# SCH_ESP8266_2025-04-25.net
KiCad netlist of a schematic drawn in EasyEDA
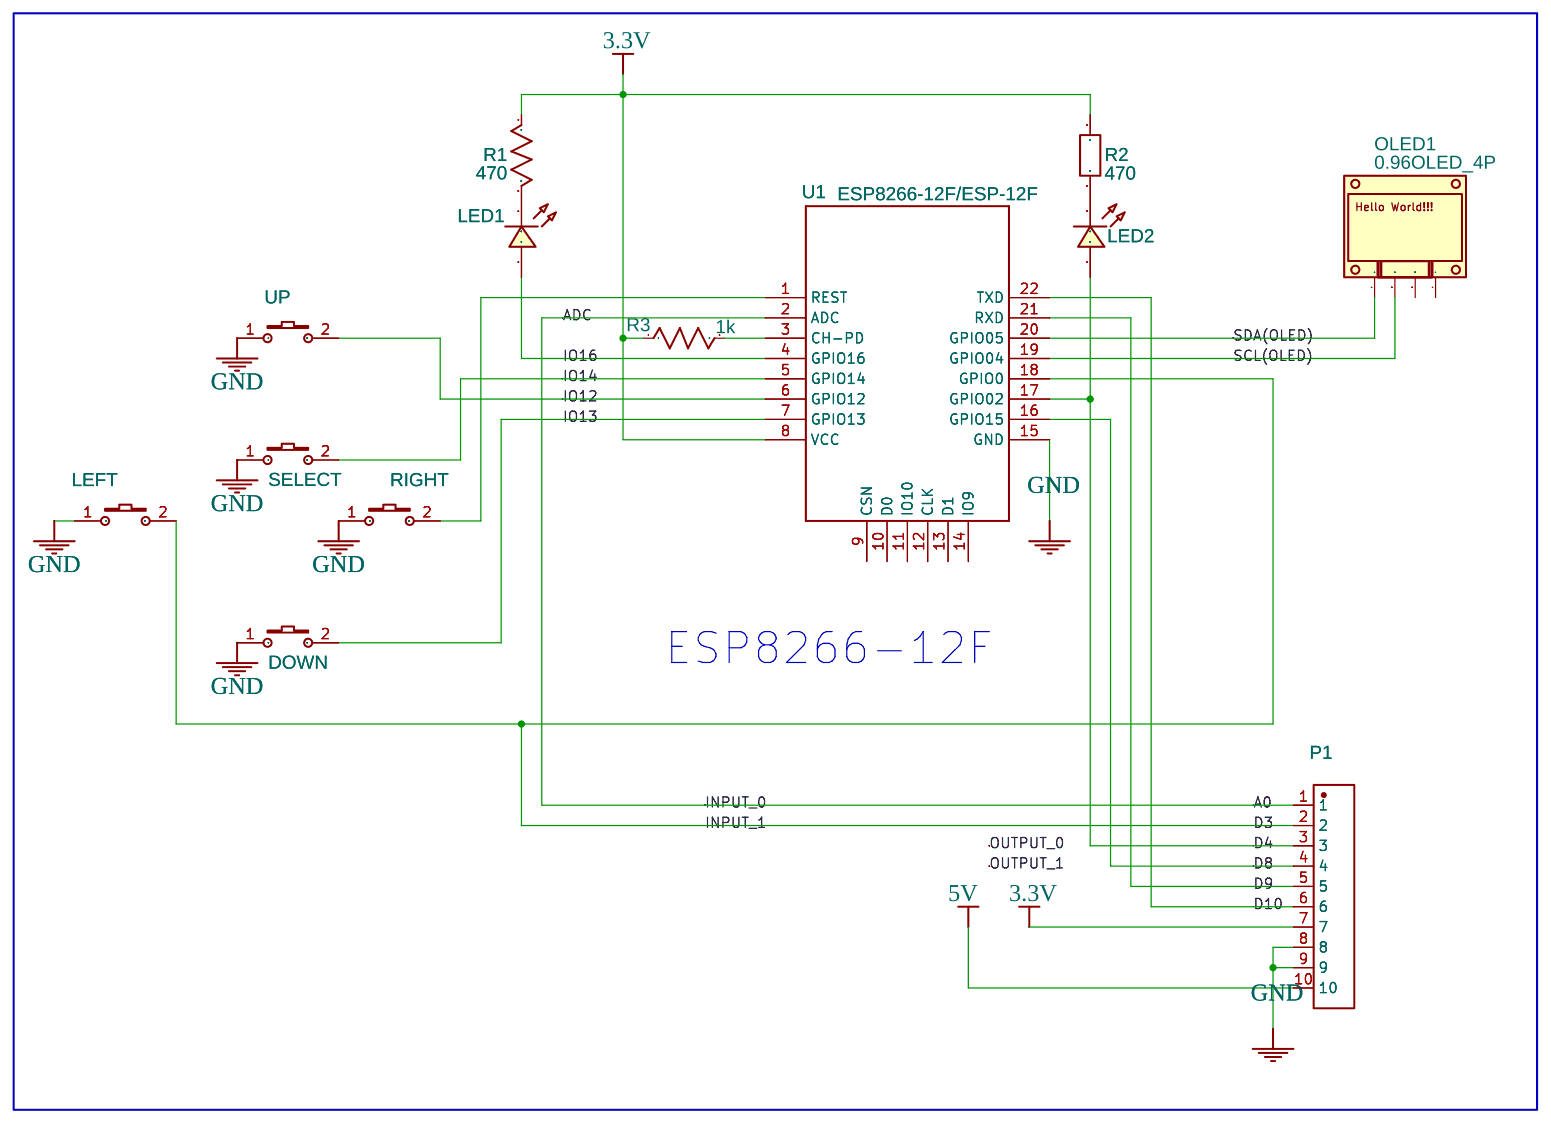
[diagram p0: ESP8266]
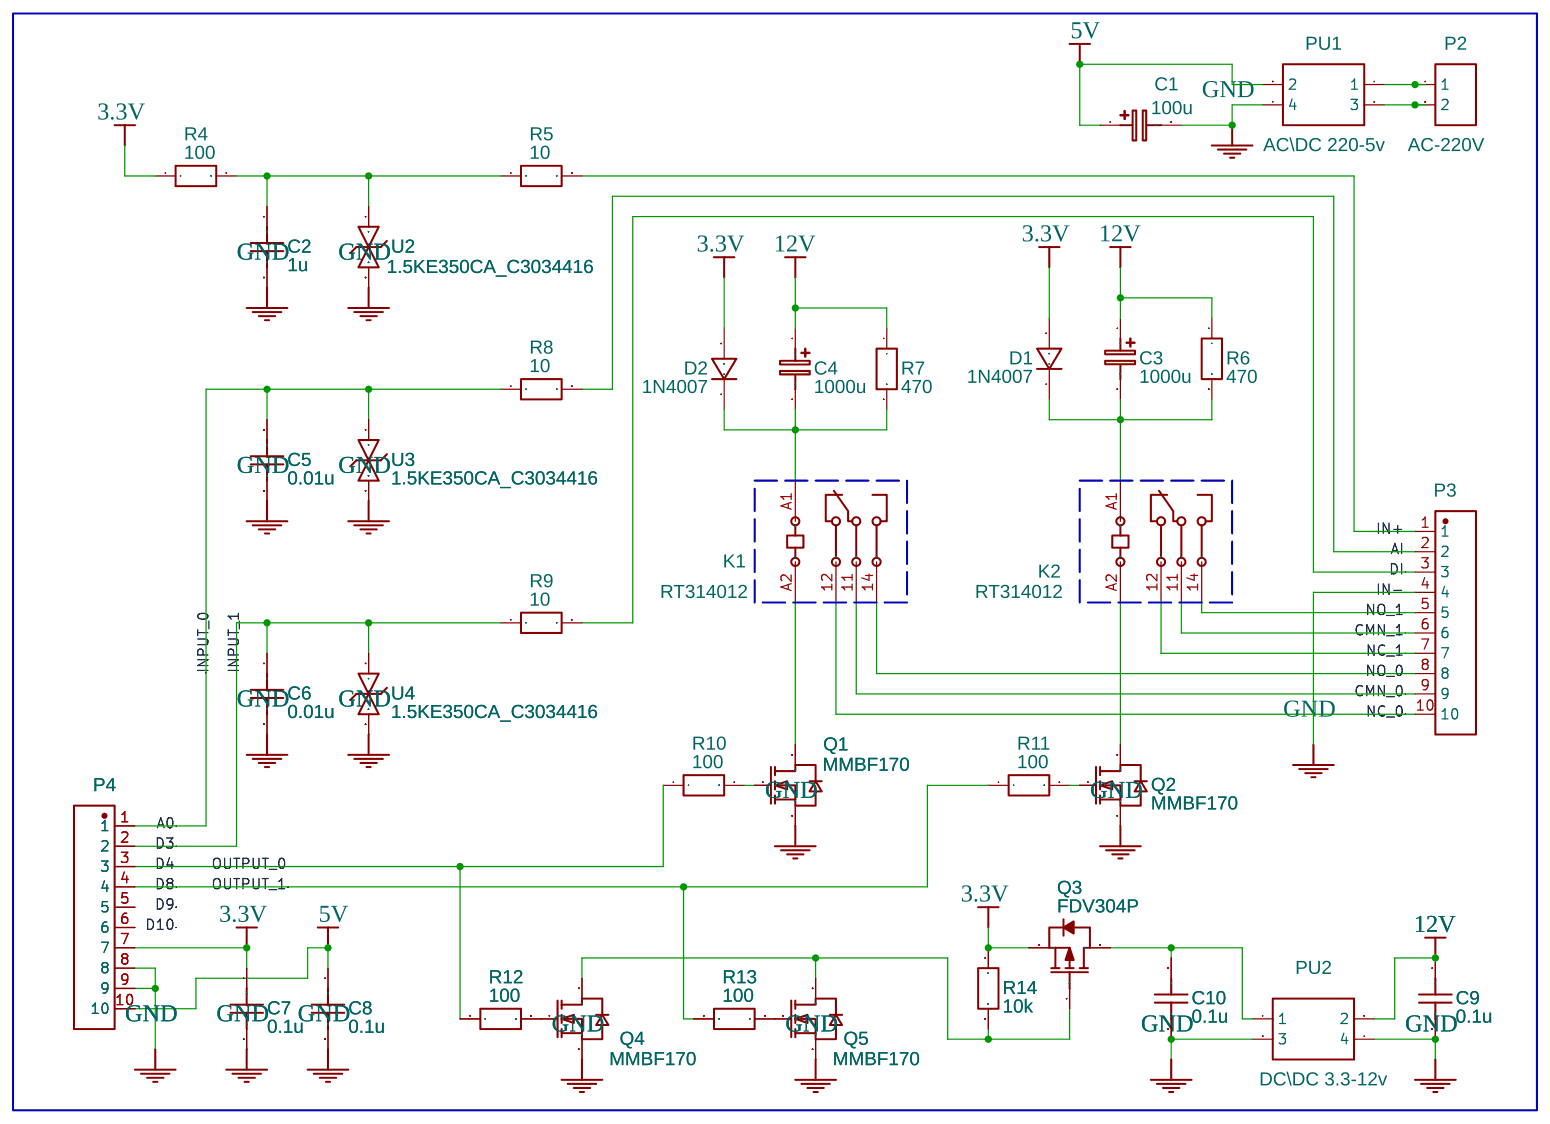
[diagram p1: Peripheral]
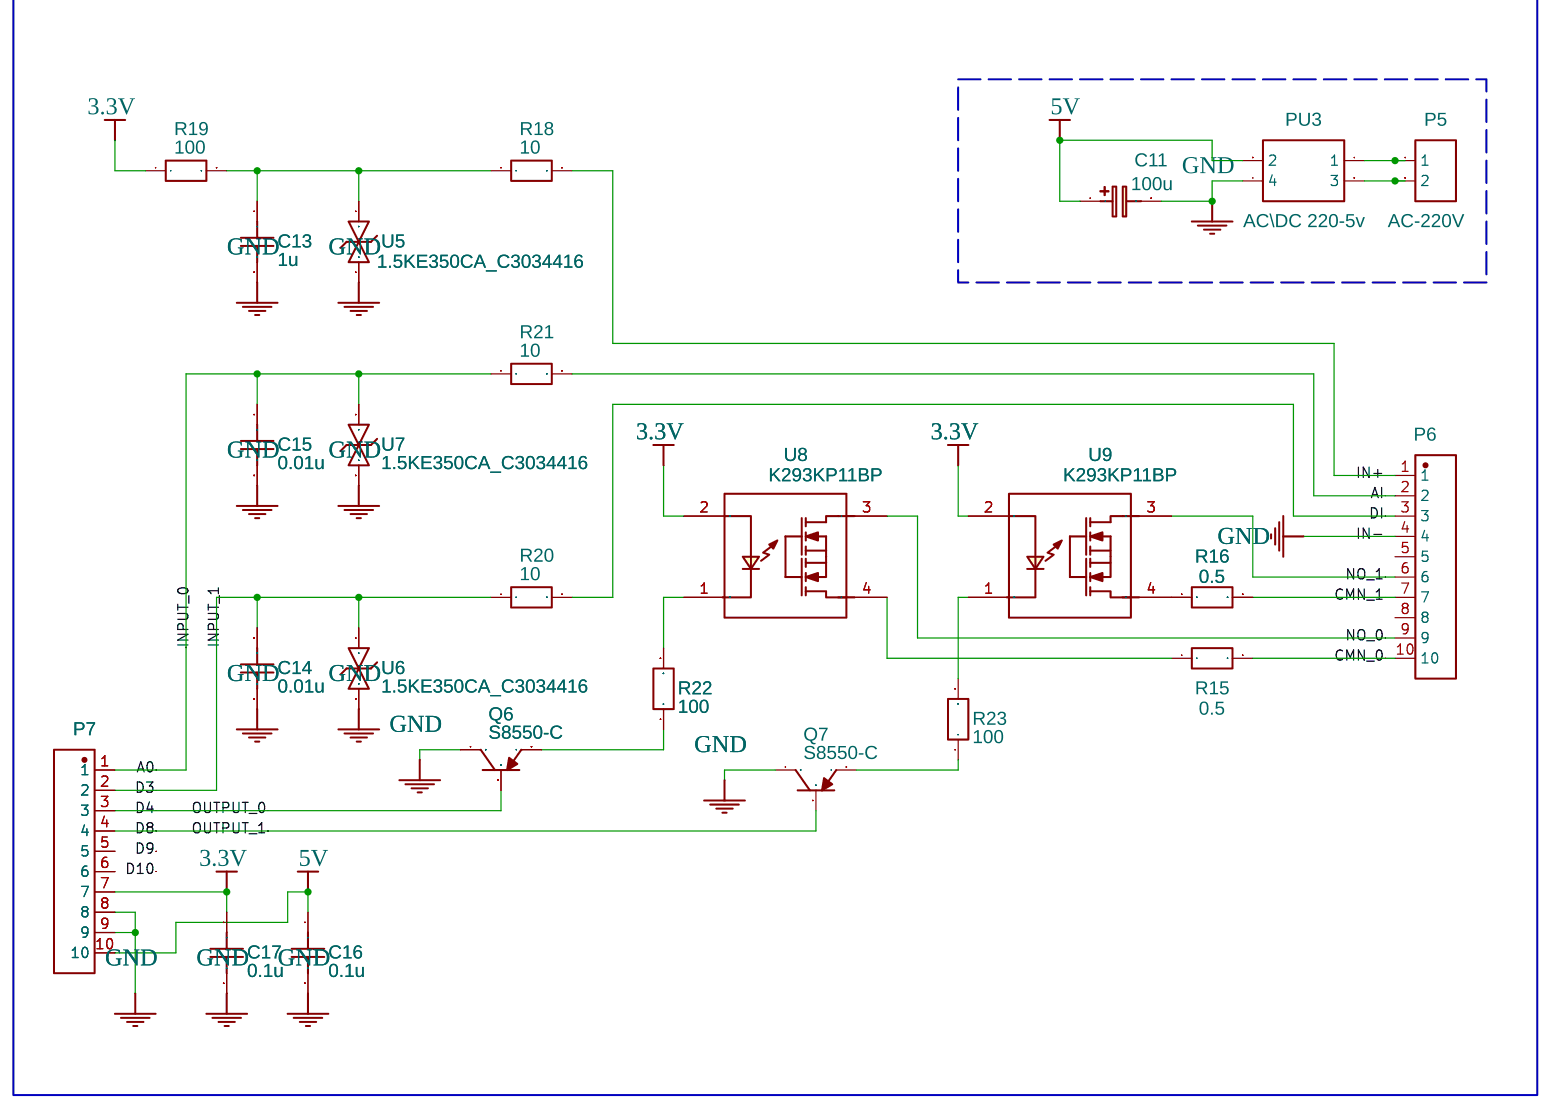
[diagram p2: Peripheral_SolidR]

(export (version "E")
  (design (tool "Eeschema 10.0.6"))
  (components
    (comp (ref "DOWN")
      (value "K2-3.6×6.1_SMD")
      (fields (field (name "Manufacturer Part") "K2-1107ST-A4SW-06"))
      (libsource (lib "") (part "K2-3.6×6.1_SMD_2"))
    )
    (comp (ref "LED1")
      (value "LED-0603_R")
      (fields
        (field (name "Manufacturer Part") "19-217/R6C-AL1M2VY/3T")
        (field (name "Manufacturer") "EVERLIGHT(台湾亿光)")
      )
      (libsource (lib "") (part "LED-0603_R"))
    )
    (comp (ref "LED2")
      (value "LED-0603_R")
      (fields
        (field (name "Manufacturer Part") "19-217/R6C-AL1M2VY/3T")
        (field (name "Manufacturer") "EVERLIGHT(台湾亿光)")
      )
      (libsource (lib "") (part "LED-0603_R"))
    )
    (comp (ref "LEFT")
      (value "K2-3.6×6.1_SMD")
      (fields (field (name "Manufacturer Part") "K2-1107ST-A4SW-06"))
      (libsource (lib "") (part "K2-3.6×6.1_SMD"))
    )
    (comp (ref "OLED1") (value "0.96OLED_4P") (libsource (lib "") (part "0.96OLED_4P")))
    (comp (ref "P1")
      (value "MTP310-1110S1")
      (fields (field (name "Manufacturer") "MINTRON(明硕)"))
      (libsource (lib "") (part "MTP310-1110S1"))
    )
    (comp (ref "R1")
      (value "470")
      (fields (field (name "Manufacturer Part") "?"))
      (libsource (lib "") (part "Resistor_1"))
    )
    (comp (ref "R2") (value "470") (libsource (lib "") (part "R_0603_EU")))
    (comp (ref "R3")
      (value "1k")
      (fields (field (name "Manufacturer Part") "?"))
      (libsource (lib "") (part "Resistor"))
    )
    (comp (ref "RIGHT")
      (value "K2-3.6×6.1_SMD")
      (fields (field (name "Manufacturer Part") "K2-1107ST-A4SW-06"))
      (libsource (lib "") (part "K2-3.6×6.1_SMD_4"))
    )
    (comp (ref "SELECT")
      (value "K2-3.6×6.1_SMD")
      (fields (field (name "Manufacturer Part") "K2-1107ST-A4SW-06"))
      (libsource (lib "") (part "K2-3.6×6.1_SMD_1"))
    )
    (comp (ref "U1")
      (value "ESP8266-12F/ESP-12F")
      (fields (field (name "Manufacturer Part") "ESP8266-12E/ESP-12E"))
      (libsource (lib "") (part "Unknown_1020_210"))
    )
    (comp (ref "UP")
      (value "K2-3.6×6.1_SMD")
      (fields (field (name "Manufacturer Part") "K2-1107ST-A4SW-06"))
      (libsource (lib "") (part "K2-3.6×6.1_SMD_3"))
    )
    (comp (ref "C1") (value "100u") (libsource (lib "") (part "C_Tan_SMD_A_EU_1")))
    (comp (ref "C2") (value "1u") (libsource (lib "") (part "C_0603_US")))
    (comp (ref "C3") (value "1000u") (libsource (lib "") (part "C_Tan_SMD_A_EU_2")))
    (comp (ref "C4") (value "1000u") (libsource (lib "") (part "C_Tan_SMD_A_EU")))
    (comp (ref "C5") (value "0.01u") (libsource (lib "") (part "C_0603_US")))
    (comp (ref "C6") (value "0.01u") (libsource (lib "") (part "C_0603_US")))
    (comp (ref "C7") (value "0.1u") (libsource (lib "") (part "C_0603_US")))
    (comp (ref "C8") (value "0.1u") (libsource (lib "") (part "C_0603_US")))
    (comp (ref "C9") (value "0.1u") (libsource (lib "") (part "C_0603_US")))
    (comp (ref "C10") (value "0.1u") (libsource (lib "") (part "C_0603_US_1")))
    (comp (ref "D1")
      (value "1N4007")
      (fields (field (name "Manufacturer") "SEMTECH"))
      (libsource (lib "") (part "1N4007"))
    )
    (comp (ref "D2")
      (value "1N4007")
      (fields (field (name "Manufacturer") "SEMTECH"))
      (libsource (lib "") (part "1N4007"))
    )
    (comp (ref "K1")
      (value "RT314012")
      (fields
        (field (name "Manufacturer Part") "RT314012F")
        (field (name "Manufacturer") "TE Connectivity(美国泰科)")
      )
      (libsource (lib "") (part "RT314012F"))
    )
    (comp (ref "K2")
      (value "RT314012")
      (fields
        (field (name "Manufacturer Part") "RT314012F")
        (field (name "Manufacturer") "TE Connectivity(美国泰科)")
      )
      (libsource (lib "") (part "RT314012F"))
    )
    (comp (ref "P2") (value "AC-220V") (libsource (lib "") (part "CONN-TH_2P-P5.00")))
    (comp (ref "P3")
      (value "MTP310-1110S1")
      (fields (field (name "Manufacturer") "MINTRON(明硕)"))
      (libsource (lib "") (part "MTP310-1110S1"))
    )
    (comp (ref "P4")
      (value "MTP310-1110S1")
      (fields (field (name "Manufacturer") "MINTRON(明硕)"))
      (libsource (lib "") (part "MTP310-1110S1_1"))
    )
    (comp (ref "PU1") (value "AC\\DC 220-5v") (libsource (lib "") (part "HDR-M-2.54_2x2_1")))
    (comp (ref "PU2") (value "DC\\DC 3.3-12v") (libsource (lib "") (part "HDR-M-2.54_2x2")))
    (comp (ref "Q1")
      (value "MMBF170")
      (fields (field (name "Manufacturer Part") "MMBF170Q-13-F") (field (name "Manufacturer") "DIODES(美台)"))
      (libsource (lib "") (part "MMBF170Q-13-F"))
    )
    (comp (ref "Q2")
      (value "MMBF170")
      (fields (field (name "Manufacturer Part") "MMBF170Q-13-F") (field (name "Manufacturer") "DIODES(美台)"))
      (libsource (lib "") (part "MMBF170Q-13-F"))
    )
    (comp (ref "Q3")
      (value "FDV304P")
      (fields (field (name "Manufacturer") "TECH PUBLIC(台舟)"))
      (libsource (lib "") (part "FDV304P_C7419961"))
    )
    (comp (ref "Q4")
      (value "MMBF170")
      (fields (field (name "Manufacturer Part") "MMBF170Q-13-F") (field (name "Manufacturer") "DIODES(美台)"))
      (libsource (lib "") (part "MMBF170Q-13-F"))
    )
    (comp (ref "Q5")
      (value "MMBF170")
      (fields (field (name "Manufacturer Part") "MMBF170Q-13-F") (field (name "Manufacturer") "DIODES(美台)"))
      (libsource (lib "") (part "MMBF170Q-13-F"))
    )
    (comp (ref "R4") (value "100") (libsource (lib "") (part "R_0603_EU")))
    (comp (ref "R5") (value "10") (libsource (lib "") (part "R_0603_EU")))
    (comp (ref "R6") (value "470") (libsource (lib "") (part "R_0603_EU_1")))
    (comp (ref "R7") (value "470") (libsource (lib "") (part "R_0603_EU_1")))
    (comp (ref "R8") (value "10") (libsource (lib "") (part "R_0603_EU")))
    (comp (ref "R9") (value "10") (libsource (lib "") (part "R_0603_EU")))
    (comp (ref "R10") (value "100") (libsource (lib "") (part "R_0603_EU")))
    (comp (ref "R11") (value "100") (libsource (lib "") (part "R_0603_EU")))
    (comp (ref "R12") (value "100") (libsource (lib "") (part "R_0603_EU")))
    (comp (ref "R13") (value "100") (libsource (lib "") (part "R_0603_EU")))
    (comp (ref "R14") (value "10k") (libsource (lib "") (part "R_0603_EU_1")))
    (comp (ref "U2")
      (value "1.5KE350CA_C3034416")
      (fields (field (name "Manufacturer Part") "1.5KE350CA") (field (name "Manufacturer") "Liown(里阳半导体)"))
      (libsource (lib "") (part "1.5KE350CA_C3034416"))
    )
    (comp (ref "U3")
      (value "1.5KE350CA_C3034416")
      (fields (field (name "Manufacturer Part") "1.5KE350CA") (field (name "Manufacturer") "Liown(里阳半导体)"))
      (libsource (lib "") (part "1.5KE350CA_C3034416"))
    )
    (comp (ref "U4")
      (value "1.5KE350CA_C3034416")
      (fields (field (name "Manufacturer Part") "1.5KE350CA") (field (name "Manufacturer") "Liown(里阳半导体)"))
      (libsource (lib "") (part "1.5KE350CA_C3034416"))
    )
    (comp (ref "C11") (value "100u") (libsource (lib "") (part "C_Tan_SMD_A_EU")))
    (comp (ref "C13") (value "1u") (libsource (lib "") (part "C_0603_US")))
    (comp (ref "C14") (value "0.01u") (libsource (lib "") (part "C_0603_US")))
    (comp (ref "C15") (value "0.01u") (libsource (lib "") (part "C_0603_US")))
    (comp (ref "C16") (value "0.1u") (libsource (lib "") (part "C_0603_US")))
    (comp (ref "C17") (value "0.1u") (libsource (lib "") (part "C_0603_US")))
    (comp (ref "P5") (value "AC-220V") (libsource (lib "") (part "CONN-TH_2P-P5.00")))
    (comp (ref "P6")
      (value "MTP310-1110S1")
      (fields (field (name "Manufacturer") "MINTRON(明硕)"))
      (libsource (lib "") (part "MTP310-1110S1_1"))
    )
    (comp (ref "P7")
      (value "MTP310-1110S1")
      (fields (field (name "Manufacturer") "MINTRON(明硕)"))
      (libsource (lib "") (part "MTP310-1110S1"))
    )
    (comp (ref "PU3") (value "AC\\DC 220-5v") (libsource (lib "") (part "HDR-M-2.54_2x2")))
    (comp (ref "Q6")
      (value "S8550-C")
      (fields (field (name "Manufacturer") "BLUE ROCKET(蓝箭)"))
      (libsource (lib "") (part "S8550-C"))
    )
    (comp (ref "Q7")
      (value "S8550-C")
      (fields (field (name "Manufacturer") "BLUE ROCKET(蓝箭)"))
      (libsource (lib "") (part "S8550-C"))
    )
    (comp (ref "R15") (value "0.5") (libsource (lib "") (part "R_0603_EU")))
    (comp (ref "R16") (value "0.5") (libsource (lib "") (part "R_0603_EU")))
    (comp (ref "R18") (value "10") (libsource (lib "") (part "R_0603_EU")))
    (comp (ref "R19") (value "100") (libsource (lib "") (part "R_0603_EU")))
    (comp (ref "R20") (value "10") (libsource (lib "") (part "R_0603_EU")))
    (comp (ref "R21") (value "10") (libsource (lib "") (part "R_0603_EU")))
    (comp (ref "R22") (value "100") (libsource (lib "") (part "R_0603_EU_1")))
    (comp (ref "R23") (value "100") (libsource (lib "") (part "R_0603_EU_1")))
    (comp (ref "U5")
      (value "1.5KE350CA_C3034416")
      (fields (field (name "Manufacturer Part") "1.5KE350CA") (field (name "Manufacturer") "Liown(里阳半导体)"))
      (libsource (lib "") (part "1.5KE350CA_C3034416"))
    )
    (comp (ref "U6")
      (value "1.5KE350CA_C3034416")
      (fields (field (name "Manufacturer Part") "1.5KE350CA") (field (name "Manufacturer") "Liown(里阳半导体)"))
      (libsource (lib "") (part "1.5KE350CA_C3034416"))
    )
    (comp (ref "U7")
      (value "1.5KE350CA_C3034416")
      (fields (field (name "Manufacturer Part") "1.5KE350CA") (field (name "Manufacturer") "Liown(里阳半导体)"))
      (libsource (lib "") (part "1.5KE350CA_C3034416"))
    )
    (comp (ref "U8")
      (value "K293KP11BP")
      (fields (field (name "Manufacturer Part") "CPC1916Y") (field (name "Manufacturer") "Littelfuse/IXYS"))
      (libsource (lib "") (part "CPC1916Y"))
    )
    (comp (ref "U9")
      (value "K293KP11BP")
      (fields (field (name "Manufacturer Part") "CPC1916Y") (field (name "Manufacturer") "Littelfuse/IXYS"))
      (libsource (lib "") (part "CPC1916Y"))
    )
  )
  (nets
    (net (code "1") (name "3.3V") (class "Default")
      (node (ref "C17") (pin "1") (pinfunction "1_1") (pintype "unspecified"))
      (node (ref "C7") (pin "1") (pinfunction "1_1") (pintype "unspecified"))
      (node (ref "D1") (pin "2") (pinfunction "2_2") (pintype "unspecified"))
      (node (ref "D2") (pin "2") (pinfunction "2_2") (pintype "unspecified"))
      (node (ref "P1") (pin "7") (pinfunction "7_7") (pintype "unspecified"))
      (node (ref "P4") (pin "7") (pinfunction "7_7") (pintype "unspecified"))
      (node (ref "P7") (pin "7") (pinfunction "7_7") (pintype "unspecified"))
      (node (ref "Q3") (pin "2") (pinfunction "S_2") (pintype "unspecified"))
      (node (ref "R1") (pin "1") (pinfunction "1_1") (pintype "unspecified"))
      (node (ref "R14") (pin "1") (pinfunction "1_1") (pintype "unspecified"))
      (node (ref "R19") (pin "1") (pinfunction "1_1") (pintype "unspecified"))
      (node (ref "R2") (pin "1") (pinfunction "1_1") (pintype "unspecified"))
      (node (ref "R3") (pin "1") (pinfunction "1_1") (pintype "unspecified"))
      (node (ref "R4") (pin "1") (pinfunction "1_1") (pintype "unspecified"))
      (node (ref "U1") (pin "8") (pinfunction "VCC_8") (pintype "unspecified"))
      (node (ref "U8") (pin "2") (pinfunction "+C_2") (pintype "unspecified"))
      (node (ref "U9") (pin "2") (pinfunction "+C_2") (pintype "unspecified"))
    )
    (net (code "2") (name "5V") (class "Default")
      (node (ref "C1") (pin "1") (pinfunction "1_1") (pintype "unspecified"))
      (node (ref "C11") (pin "1") (pinfunction "1_1") (pintype "unspecified"))
      (node (ref "C16") (pin "1") (pinfunction "1_1") (pintype "unspecified"))
      (node (ref "C8") (pin "1") (pinfunction "1_1") (pintype "unspecified"))
      (node (ref "P1") (pin "10") (pinfunction "10_10") (pintype "unspecified"))
      (node (ref "P4") (pin "10") (pinfunction "10_10") (pintype "unspecified"))
      (node (ref "P7") (pin "10") (pinfunction "10_10") (pintype "unspecified"))
      (node (ref "PU1") (pin "2") (pinfunction "2_2") (pintype "input"))
      (node (ref "PU3") (pin "2") (pinfunction "2_2") (pintype "input"))
    )
    (net (code "3") (name "12V") (class "Default")
      (node (ref "C3") (pin "1") (pinfunction "1_1") (pintype "unspecified"))
      (node (ref "C4") (pin "1") (pinfunction "1_1") (pintype "unspecified"))
      (node (ref "C9") (pin "1") (pinfunction "1_1") (pintype "unspecified"))
      (node (ref "PU2") (pin "2") (pinfunction "2_2") (pintype "input"))
      (node (ref "R6") (pin "1") (pinfunction "1_1") (pintype "unspecified"))
      (node (ref "R7") (pin "1") (pinfunction "1_1") (pintype "unspecified"))
    )
    (net (code "4") (name "A0") (class "Default")
      (node (ref "C15") (pin "1") (pinfunction "1_1") (pintype "unspecified"))
      (node (ref "C5") (pin "1") (pinfunction "1_1") (pintype "unspecified"))
      (node (ref "P1") (pin "1") (pinfunction "1_1") (pintype "unspecified"))
      (node (ref "P4") (pin "1") (pinfunction "1_1") (pintype "unspecified"))
      (node (ref "P7") (pin "1") (pinfunction "1_1") (pintype "unspecified"))
      (node (ref "R21") (pin "1") (pinfunction "1_1") (pintype "unspecified"))
      (node (ref "R8") (pin "1") (pinfunction "1_1") (pintype "unspecified"))
      (node (ref "U1") (pin "2") (pinfunction "ADC_2") (pintype "unspecified"))
      (node (ref "U3") (pin "1") (pinfunction "1_1") (pintype "unspecified"))
      (node (ref "U7") (pin "1") (pinfunction "1_1") (pintype "unspecified"))
    )
    (net (code "5") (name "AI") (class "Default")
      (node (ref "P3") (pin "2") (pinfunction "2_2") (pintype "unspecified"))
      (node (ref "P6") (pin "2") (pinfunction "2_2") (pintype "unspecified"))
      (node (ref "R21") (pin "2") (pinfunction "2_2") (pintype "unspecified"))
      (node (ref "R8") (pin "2") (pinfunction "2_2") (pintype "unspecified"))
    )
    (net (code "6") (name "CMN_0") (class "Default")
      (node (ref "K1") (pin "11") (pinfunction "11_11") (pintype "unspecified"))
      (node (ref "P3") (pin "9") (pinfunction "9_9") (pintype "unspecified"))
      (node (ref "P6") (pin "10") (pinfunction "10_10") (pintype "unspecified"))
      (node (ref "R15") (pin "2") (pinfunction "2_2") (pintype "unspecified"))
    )
    (net (code "7") (name "CMN_1") (class "Default")
      (node (ref "K2") (pin "11") (pinfunction "11_11") (pintype "unspecified"))
      (node (ref "P3") (pin "6") (pinfunction "6_6") (pintype "unspecified"))
      (node (ref "P6") (pin "7") (pinfunction "7_7") (pintype "unspecified"))
      (node (ref "R16") (pin "2") (pinfunction "2_2") (pintype "unspecified"))
    )
    (net (code "8") (name "D3") (class "Default")
      (node (ref "C14") (pin "1") (pinfunction "1_1") (pintype "unspecified"))
      (node (ref "C6") (pin "1") (pinfunction "1_1") (pintype "unspecified"))
      (node (ref "LEFT") (pin "2") (pinfunction "2_2") (pintype "unspecified"))
      (node (ref "P1") (pin "2") (pinfunction "2_2") (pintype "unspecified"))
      (node (ref "P4") (pin "2") (pinfunction "2_2") (pintype "unspecified"))
      (node (ref "P7") (pin "2") (pinfunction "2_2") (pintype "unspecified"))
      (node (ref "R20") (pin "1") (pinfunction "1_1") (pintype "unspecified"))
      (node (ref "R9") (pin "1") (pinfunction "1_1") (pintype "unspecified"))
      (node (ref "U1") (pin "18") (pinfunction "GPIO0_18") (pintype "unspecified"))
      (node (ref "U4") (pin "1") (pinfunction "1_1") (pintype "unspecified"))
      (node (ref "U6") (pin "1") (pinfunction "1_1") (pintype "unspecified"))
    )
    (net (code "9") (name "D4") (class "Default")
      (node (ref "LED2") (pin "1") (pinfunction "1_1") (pintype "unspecified"))
      (node (ref "P1") (pin "3") (pinfunction "3_3") (pintype "unspecified"))
      (node (ref "P4") (pin "3") (pinfunction "3_3") (pintype "unspecified"))
      (node (ref "P7") (pin "3") (pinfunction "3_3") (pintype "unspecified"))
      (node (ref "Q6") (pin "2") (pinfunction "B_2") (pintype "input"))
      (node (ref "R10") (pin "1") (pinfunction "1_1") (pintype "unspecified"))
      (node (ref "R12") (pin "1") (pinfunction "1_1") (pintype "unspecified"))
      (node (ref "U1") (pin "17") (pinfunction "GPIO02_17") (pintype "unspecified"))
    )
    (net (code "10") (name "D8") (class "Default")
      (node (ref "P1") (pin "4") (pinfunction "4_4") (pintype "unspecified"))
      (node (ref "P4") (pin "4") (pinfunction "4_4") (pintype "unspecified"))
      (node (ref "P7") (pin "4") (pinfunction "4_4") (pintype "unspecified"))
      (node (ref "Q7") (pin "2") (pinfunction "B_2") (pintype "input"))
      (node (ref "R11") (pin "1") (pinfunction "1_1") (pintype "unspecified"))
      (node (ref "R13") (pin "1") (pinfunction "1_1") (pintype "unspecified"))
      (node (ref "U1") (pin "16") (pinfunction "GPIO15_16") (pintype "unspecified"))
    )
    (net (code "11") (name "D9") (class "Default")
      (node (ref "P1") (pin "5") (pinfunction "5_5") (pintype "unspecified"))
      (node (ref "U1") (pin "21") (pinfunction "RXD_21") (pintype "unspecified"))
    )
    (net (code "12") (name "D10") (class "Default")
      (node (ref "P1") (pin "6") (pinfunction "6_6") (pintype "unspecified"))
      (node (ref "U1") (pin "22") (pinfunction "TXD_22") (pintype "unspecified"))
    )
    (net (code "13") (name "DI") (class "Default")
      (node (ref "P3") (pin "3") (pinfunction "3_3") (pintype "unspecified"))
      (node (ref "P6") (pin "3") (pinfunction "3_3") (pintype "unspecified"))
      (node (ref "R20") (pin "2") (pinfunction "2_2") (pintype "unspecified"))
      (node (ref "R9") (pin "2") (pinfunction "2_2") (pintype "unspecified"))
    )
    (net (code "14") (name "IN+") (class "Default")
      (node (ref "P3") (pin "1") (pinfunction "1_1") (pintype "unspecified"))
      (node (ref "P6") (pin "1") (pinfunction "1_1") (pintype "unspecified"))
      (node (ref "R18") (pin "2") (pinfunction "2_2") (pintype "unspecified"))
      (node (ref "R5") (pin "2") (pinfunction "2_2") (pintype "unspecified"))
    )
    (net (code "15") (name "IN-") (class "Default")
      (node (ref "C1") (pin "2") (pinfunction "2_2") (pintype "unspecified"))
      (node (ref "C10") (pin "1") (pinfunction "1_1") (pintype "unspecified"))
      (node (ref "C11") (pin "2") (pinfunction "2_2") (pintype "unspecified"))
      (node (ref "C13") (pin "2") (pinfunction "2_2") (pintype "unspecified"))
      (node (ref "C14") (pin "2") (pinfunction "2_2") (pintype "unspecified"))
      (node (ref "C15") (pin "2") (pinfunction "2_2") (pintype "unspecified"))
      (node (ref "C16") (pin "2") (pinfunction "2_2") (pintype "unspecified"))
      (node (ref "C17") (pin "2") (pinfunction "2_2") (pintype "unspecified"))
      (node (ref "C2") (pin "2") (pinfunction "2_2") (pintype "unspecified"))
      (node (ref "C5") (pin "2") (pinfunction "2_2") (pintype "unspecified"))
      (node (ref "C6") (pin "2") (pinfunction "2_2") (pintype "unspecified"))
      (node (ref "C7") (pin "2") (pinfunction "2_2") (pintype "unspecified"))
      (node (ref "C8") (pin "2") (pinfunction "2_2") (pintype "unspecified"))
      (node (ref "C9") (pin "2") (pinfunction "2_2") (pintype "unspecified"))
      (node (ref "DOWN") (pin "1") (pinfunction "1_1") (pintype "unspecified"))
      (node (ref "LEFT") (pin "1") (pinfunction "1_1") (pintype "unspecified"))
      (node (ref "P1") (pin "8") (pinfunction "8_8") (pintype "unspecified"))
      (node (ref "P1") (pin "9") (pinfunction "9_9") (pintype "unspecified"))
      (node (ref "P3") (pin "4") (pinfunction "4_4") (pintype "unspecified"))
      (node (ref "P4") (pin "8") (pinfunction "8_8") (pintype "unspecified"))
      (node (ref "P4") (pin "9") (pinfunction "9_9") (pintype "unspecified"))
      (node (ref "P6") (pin "4") (pinfunction "4_4") (pintype "unspecified"))
      (node (ref "P7") (pin "8") (pinfunction "8_8") (pintype "unspecified"))
      (node (ref "P7") (pin "9") (pinfunction "9_9") (pintype "unspecified"))
      (node (ref "PU1") (pin "4") (pinfunction "4_4") (pintype "input"))
      (node (ref "PU2") (pin "3") (pinfunction "3_3") (pintype "input"))
      (node (ref "PU2") (pin "4") (pinfunction "4_4") (pintype "input"))
      (node (ref "PU3") (pin "4") (pinfunction "4_4") (pintype "input"))
      (node (ref "Q1") (pin "2") (pinfunction "S_2") (pintype "unspecified"))
      (node (ref "Q2") (pin "2") (pinfunction "S_2") (pintype "unspecified"))
      (node (ref "Q4") (pin "2") (pinfunction "S_2") (pintype "unspecified"))
      (node (ref "Q5") (pin "2") (pinfunction "S_2") (pintype "unspecified"))
      (node (ref "Q6") (pin "1") (pinfunction "C_1") (pintype "input"))
      (node (ref "Q7") (pin "1") (pinfunction "C_1") (pintype "input"))
      (node (ref "RIGHT") (pin "1") (pinfunction "1_1") (pintype "unspecified"))
      (node (ref "SELECT") (pin "1") (pinfunction "1_1") (pintype "unspecified"))
      (node (ref "U1") (pin "15") (pinfunction "GND_15") (pintype "unspecified"))
      (node (ref "U2") (pin "2") (pinfunction "2_2") (pintype "unspecified"))
      (node (ref "U3") (pin "2") (pinfunction "2_2") (pintype "unspecified"))
      (node (ref "U4") (pin "2") (pinfunction "2_2") (pintype "unspecified"))
      (node (ref "U5") (pin "2") (pinfunction "2_2") (pintype "unspecified"))
      (node (ref "U6") (pin "2") (pinfunction "2_2") (pintype "unspecified"))
      (node (ref "U7") (pin "2") (pinfunction "2_2") (pintype "unspecified"))
      (node (ref "UP") (pin "1") (pinfunction "1_1") (pintype "unspecified"))
    )
    (net (code "16") (name "IO12") (class "Default")
      (node (ref "U1") (pin "6") (pinfunction "GPIO12_6") (pintype "unspecified"))
      (node (ref "UP") (pin "2") (pinfunction "2_2") (pintype "unspecified"))
    )
    (net (code "17") (name "IO13") (class "Default")
      (node (ref "DOWN") (pin "2") (pinfunction "2_2") (pintype "unspecified"))
      (node (ref "U1") (pin "7") (pinfunction "GPIO13_7") (pintype "unspecified"))
    )
    (net (code "18") (name "IO14") (class "Default")
      (node (ref "SELECT") (pin "2") (pinfunction "2_2") (pintype "unspecified"))
      (node (ref "U1") (pin "5") (pinfunction "GPIO14_5") (pintype "unspecified"))
    )
    (net (code "19") (name "IO16") (class "Default")
      (node (ref "LED1") (pin "1") (pinfunction "1_1") (pintype "unspecified"))
      (node (ref "U1") (pin "4") (pinfunction "GPIO16_4") (pintype "unspecified"))
    )
    (net (code "20") (name "NC_0") (class "Default")
      (node (ref "K1") (pin "12") (pinfunction "12_12") (pintype "unspecified"))
      (node (ref "P3") (pin "10") (pinfunction "10_10") (pintype "unspecified"))
    )
    (net (code "21") (name "NC_1") (class "Default")
      (node (ref "K2") (pin "12") (pinfunction "12_12") (pintype "unspecified"))
      (node (ref "P3") (pin "7") (pinfunction "7_7") (pintype "unspecified"))
    )
    (net (code "22") (name "NO_0") (class "Default")
      (node (ref "K1") (pin "14") (pinfunction "14_14") (pintype "unspecified"))
      (node (ref "P3") (pin "8") (pinfunction "8_8") (pintype "unspecified"))
      (node (ref "P6") (pin "9") (pinfunction "9_9") (pintype "unspecified"))
      (node (ref "U8") (pin "3") (pinfunction "L_3") (pintype "unspecified"))
    )
    (net (code "23") (name "NO_1") (class "Default")
      (node (ref "K2") (pin "14") (pinfunction "14_14") (pintype "unspecified"))
      (node (ref "P3") (pin "5") (pinfunction "5_5") (pintype "unspecified"))
      (node (ref "P6") (pin "6") (pinfunction "6_6") (pintype "unspecified"))
      (node (ref "U9") (pin "3") (pinfunction "L_3") (pintype "unspecified"))
    )
    (net (code "24") (name "Net-(C2-Pad1)") (class "Default")
      (node (ref "C2") (pin "1") (pinfunction "1_1") (pintype "unspecified"))
      (node (ref "R4") (pin "2") (pinfunction "2_2") (pintype "unspecified"))
      (node (ref "R5") (pin "1") (pinfunction "1_1") (pintype "unspecified"))
      (node (ref "U2") (pin "1") (pinfunction "1_1") (pintype "unspecified"))
    )
    (net (code "25") (name "Net-(C3-Pad2)") (class "Default")
      (node (ref "C3") (pin "2") (pinfunction "2_2") (pintype "unspecified"))
      (node (ref "D1") (pin "1") (pinfunction "1_1") (pintype "unspecified"))
      (node (ref "K2") (pin "A1") (pinfunction "A1_A1") (pintype "unspecified"))
      (node (ref "R6") (pin "2") (pinfunction "2_2") (pintype "unspecified"))
    )
    (net (code "26") (name "Net-(C4-Pad2)") (class "Default")
      (node (ref "C4") (pin "2") (pinfunction "2_2") (pintype "unspecified"))
      (node (ref "D2") (pin "1") (pinfunction "1_1") (pintype "unspecified"))
      (node (ref "K1") (pin "A1") (pinfunction "A1_A1") (pintype "unspecified"))
      (node (ref "R7") (pin "2") (pinfunction "2_2") (pintype "unspecified"))
    )
    (net (code "27") (name "Net-(C13-Pad1)") (class "Default")
      (node (ref "C13") (pin "1") (pinfunction "1_1") (pintype "unspecified"))
      (node (ref "R18") (pin "1") (pinfunction "1_1") (pintype "unspecified"))
      (node (ref "R19") (pin "2") (pinfunction "2_2") (pintype "unspecified"))
      (node (ref "U5") (pin "1") (pinfunction "1_1") (pintype "unspecified"))
    )
    (net (code "28") (name "Net-(LED1-Pad2)") (class "Default")
      (node (ref "LED1") (pin "2") (pinfunction "2_2") (pintype "unspecified"))
      (node (ref "R1") (pin "2") (pinfunction "2_2") (pintype "unspecified"))
    )
    (net (code "29") (name "Net-(LED2-Pad2)") (class "Default")
      (node (ref "LED2") (pin "2") (pinfunction "2_2") (pintype "unspecified"))
      (node (ref "R2") (pin "2") (pinfunction "2_2") (pintype "unspecified"))
    )
    (net (code "30") (name "Net-(P2-Pad1)") (class "Default")
      (node (ref "P2") (pin "1") (pinfunction "1_1") (pintype "unspecified"))
      (node (ref "PU1") (pin "1") (pinfunction "1_1") (pintype "input"))
    )
    (net (code "31") (name "Net-(P2-Pad2)") (class "Default")
      (node (ref "P2") (pin "2") (pinfunction "2_2") (pintype "unspecified"))
      (node (ref "PU1") (pin "3") (pinfunction "3_3") (pintype "input"))
    )
    (net (code "32") (name "Net-(P5-Pad1)") (class "Default")
      (node (ref "P5") (pin "1") (pinfunction "1_1") (pintype "unspecified"))
      (node (ref "PU3") (pin "1") (pinfunction "1_1") (pintype "input"))
    )
    (net (code "33") (name "Net-(P5-Pad2)") (class "Default")
      (node (ref "P5") (pin "2") (pinfunction "2_2") (pintype "unspecified"))
      (node (ref "PU3") (pin "3") (pinfunction "3_3") (pintype "input"))
    )
    (net (code "34") (name "Net-(Q1-D)") (class "Default")
      (node (ref "K1") (pin "A2") (pinfunction "A2_A2") (pintype "unspecified"))
      (node (ref "Q1") (pin "3") (pinfunction "D_3") (pintype "unspecified"))
    )
    (net (code "35") (name "Net-(Q1-G)") (class "Default")
      (node (ref "Q1") (pin "1") (pinfunction "G_1") (pintype "unspecified"))
      (node (ref "R10") (pin "2") (pinfunction "2_2") (pintype "unspecified"))
    )
    (net (code "36") (name "Net-(Q2-D)") (class "Default")
      (node (ref "K2") (pin "A2") (pinfunction "A2_A2") (pintype "unspecified"))
      (node (ref "Q2") (pin "3") (pinfunction "D_3") (pintype "unspecified"))
    )
    (net (code "37") (name "Net-(Q2-G)") (class "Default")
      (node (ref "Q2") (pin "1") (pinfunction "G_1") (pintype "unspecified"))
      (node (ref "R11") (pin "2") (pinfunction "2_2") (pintype "unspecified"))
    )
    (net (code "38") (name "Net-(Q3-D)") (class "Default")
      (node (ref "C10") (pin "2") (pinfunction "2_2") (pintype "unspecified"))
      (node (ref "PU2") (pin "1") (pinfunction "1_1") (pintype "input"))
      (node (ref "Q3") (pin "3") (pinfunction "D_3") (pintype "unspecified"))
    )
    (net (code "39") (name "Net-(Q3-G)") (class "Default")
      (node (ref "Q3") (pin "1") (pinfunction "G_1") (pintype "unspecified"))
      (node (ref "Q4") (pin "3") (pinfunction "D_3") (pintype "unspecified"))
      (node (ref "Q5") (pin "3") (pinfunction "D_3") (pintype "unspecified"))
      (node (ref "R14") (pin "2") (pinfunction "2_2") (pintype "unspecified"))
    )
    (net (code "40") (name "Net-(Q4-G)") (class "Default")
      (node (ref "Q4") (pin "1") (pinfunction "G_1") (pintype "unspecified"))
      (node (ref "R12") (pin "2") (pinfunction "2_2") (pintype "unspecified"))
    )
    (net (code "41") (name "Net-(Q5-G)") (class "Default")
      (node (ref "Q5") (pin "1") (pinfunction "G_1") (pintype "unspecified"))
      (node (ref "R13") (pin "2") (pinfunction "2_2") (pintype "unspecified"))
    )
    (net (code "42") (name "Net-(Q6-E)") (class "Default")
      (node (ref "Q6") (pin "3") (pinfunction "E_3") (pintype "input"))
      (node (ref "R22") (pin "1") (pinfunction "1_1") (pintype "unspecified"))
    )
    (net (code "43") (name "Net-(Q7-E)") (class "Default")
      (node (ref "Q7") (pin "3") (pinfunction "E_3") (pintype "input"))
      (node (ref "R23") (pin "1") (pinfunction "1_1") (pintype "unspecified"))
    )
    (net (code "44") (name "Net-(R15-Pad1)") (class "Default")
      (node (ref "R15") (pin "1") (pinfunction "1_1") (pintype "unspecified"))
      (node (ref "U8") (pin "4") (pinfunction "L_4") (pintype "unspecified"))
    )
    (net (code "45") (name "Net-(R16-Pad1)") (class "Default")
      (node (ref "R16") (pin "1") (pinfunction "1_1") (pintype "unspecified"))
      (node (ref "U9") (pin "4") (pinfunction "L_4") (pintype "unspecified"))
    )
    (net (code "46") (name "Net-(U1-CH-PD)") (class "Default")
      (node (ref "R3") (pin "2") (pinfunction "2_2") (pintype "unspecified"))
      (node (ref "U1") (pin "3") (pinfunction "CH-PD_3") (pintype "unspecified"))
    )
    (net (code "47") (name "Net-(U1-REST)") (class "Default")
      (node (ref "RIGHT") (pin "2") (pinfunction "2_2") (pintype "unspecified"))
      (node (ref "U1") (pin "1") (pinfunction "REST_1") (pintype "unspecified"))
    )
    (net (code "48") (name "Net-(U8--+C)") (class "Default")
      (node (ref "R22") (pin "2") (pinfunction "2_2") (pintype "unspecified"))
      (node (ref "U8") (pin "1") (pinfunction "-+C_1") (pintype "unspecified"))
    )
    (net (code "49") (name "Net-(U9--+C)") (class "Default")
      (node (ref "R23") (pin "2") (pinfunction "2_2") (pintype "unspecified"))
      (node (ref "U9") (pin "1") (pinfunction "-+C_1") (pintype "unspecified"))
    )
    (net (code "50") (name "SCL(OLED)") (class "Default")
      (node (ref "OLED1") (pin "2") (pinfunction "2_2") (pintype "unspecified"))
      (node (ref "U1") (pin "19") (pinfunction "GPIO04_19") (pintype "unspecified"))
    )
    (net (code "51") (name "SDA(OLED)") (class "Default")
      (node (ref "OLED1") (pin "1") (pinfunction "1_1") (pintype "unspecified"))
      (node (ref "U1") (pin "20") (pinfunction "GPIO05_20") (pintype "unspecified"))
    )
    (net (code "52") (name "unconnected-(OLED1-Pad3)") (class "Default")
      (node (ref "OLED1") (pin "3") (pinfunction "3_3") (pintype "unspecified"))
    )
    (net (code "53") (name "unconnected-(OLED1-Pad4)") (class "Default")
      (node (ref "OLED1") (pin "4") (pinfunction "4_4") (pintype "unspecified"))
    )
    (net (code "54") (name "unconnected-(P4-Pad5)") (class "Default")
      (node (ref "P4") (pin "5") (pinfunction "5_5") (pintype "unspecified"))
    )
    (net (code "55") (name "unconnected-(P4-Pad6)") (class "Default")
      (node (ref "P4") (pin "6") (pinfunction "6_6") (pintype "unspecified"))
    )
    (net (code "56") (name "unconnected-(P6-Pad5)") (class "Default")
      (node (ref "P6") (pin "5") (pinfunction "5_5") (pintype "unspecified"))
    )
    (net (code "57") (name "unconnected-(P6-Pad8)") (class "Default")
      (node (ref "P6") (pin "8") (pinfunction "8_8") (pintype "unspecified"))
    )
    (net (code "58") (name "unconnected-(P7-Pad5)") (class "Default")
      (node (ref "P7") (pin "5") (pinfunction "5_5") (pintype "unspecified"))
    )
    (net (code "59") (name "unconnected-(P7-Pad6)") (class "Default")
      (node (ref "P7") (pin "6") (pinfunction "6_6") (pintype "unspecified"))
    )
    (net (code "60") (name "unconnected-(U1-CLK-Pad12)") (class "Default")
      (node (ref "U1") (pin "12") (pinfunction "CLK_12") (pintype "unspecified"))
    )
    (net (code "61") (name "unconnected-(U1-CSN-Pad9)") (class "Default")
      (node (ref "U1") (pin "9") (pinfunction "CSN_9") (pintype "unspecified"))
    )
    (net (code "62") (name "unconnected-(U1-D0-Pad10)") (class "Default")
      (node (ref "U1") (pin "10") (pinfunction "D0_10") (pintype "unspecified"))
    )
    (net (code "63") (name "unconnected-(U1-D1-Pad13)") (class "Default")
      (node (ref "U1") (pin "13") (pinfunction "D1_13") (pintype "unspecified"))
    )
    (net (code "64") (name "unconnected-(U1-IO9-Pad14)") (class "Default")
      (node (ref "U1") (pin "14") (pinfunction "IO9_14") (pintype "unspecified"))
    )
    (net (code "65") (name "unconnected-(U1-IO10-Pad11)") (class "Default")
      (node (ref "U1") (pin "11") (pinfunction "IO10_11") (pintype "unspecified"))
    )
  )
)
